# Power_Embedded_Board_Top.net
KiCad netlist of a schematic drawn in Altium Designer
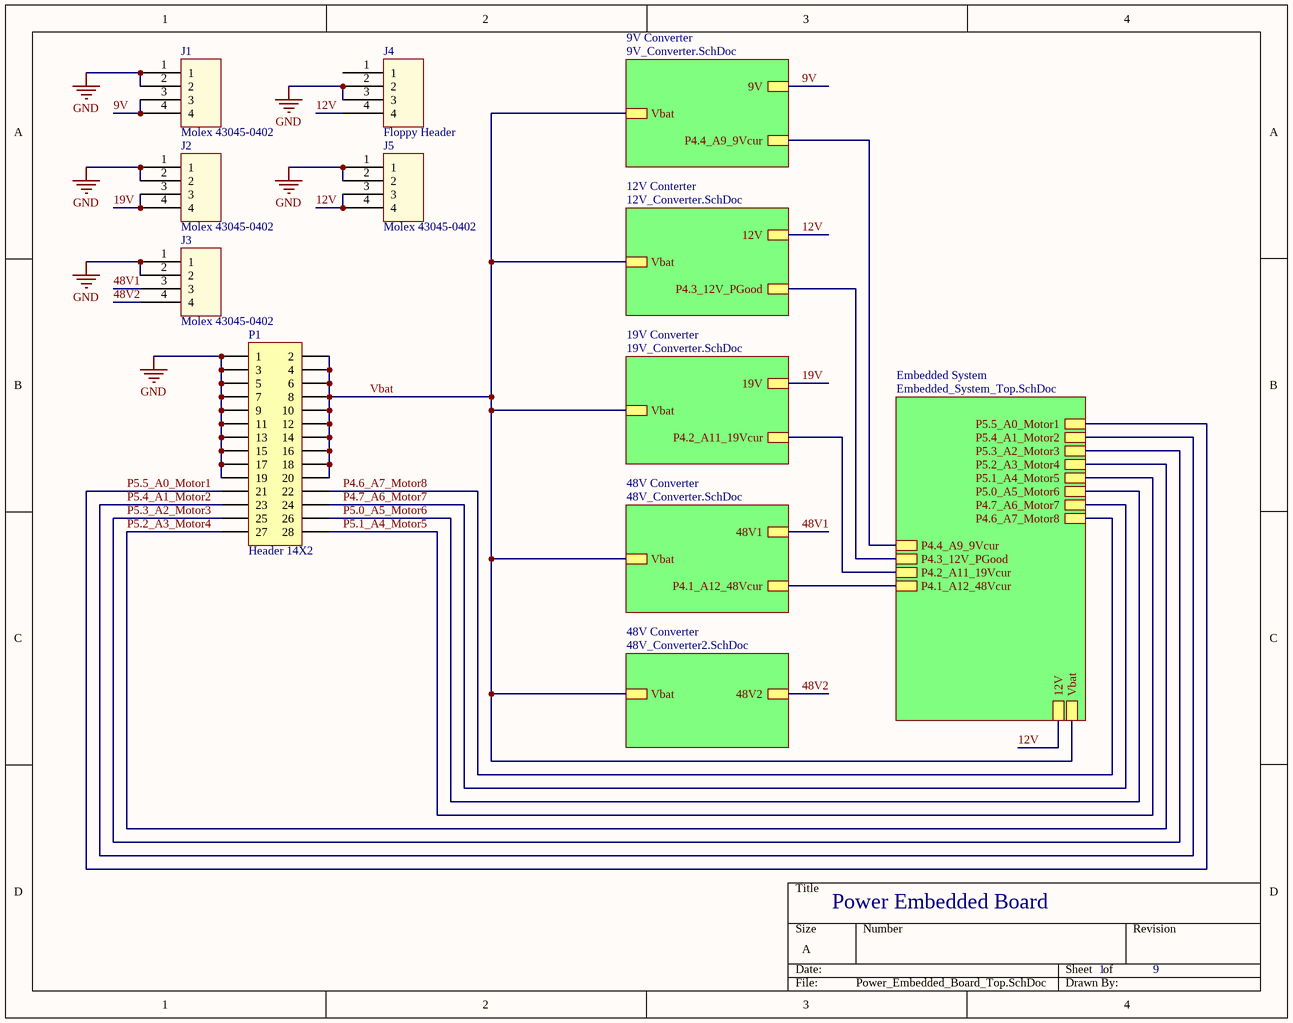
[diagram p0: Power_Embedded_Board_Top.SchDoc]

(export (version "E")
  (design (tool "Eeschema 10.0.6"))
  (components
    (comp (ref "J1")
      (value "Molex 43045-0402")
      (footprint "Molex43045-0402")
      (libsource (lib "Power_Embedded_Board_Library") (part "Molex43045-0402"))
    )
    (comp (ref "J2")
      (value "Molex 43045-0402")
      (footprint "Molex43045-0402")
      (libsource (lib "Power_Embedded_Board_Library") (part "Molex43045-0402"))
    )
    (comp (ref "J3")
      (value "Molex 43045-0402")
      (footprint "Molex43045-0402")
      (libsource (lib "Power_Embedded_Board_Library") (part "Molex43045-0402"))
    )
    (comp (ref "J4")
      (value "Floppy Header")
      (footprint "Header 1x4 12V")
      (libsource (lib "Power_Embedded_Board_Library") (part "Molex43045-0402"))
    )
    (comp (ref "J5")
      (value "Molex 43045-0402")
      (footprint "Molex43045-0402")
      (libsource (lib "Power_Embedded_Board_Library") (part "Molex43045-0402"))
    )
    (comp (ref "P1")
      (value "Header 14X2")
      (footprint "Header 2x14")
      (description "Header, 14-Pin, Dual row")
      (fields (field (name "PUBLISHER") "Altium Limited"))
      (libsource (lib "Miscellaneous Connectors") (part "Header 14X2"))
    )
  )
  (nets
    (net (code "1") (name "/9V") (class "Default")
      (node (ref "J1") (pin "3") (pinfunction "3_3") (pintype "passive"))
      (node (ref "J1") (pin "4") (pinfunction "4_4") (pintype "passive"))
    )
    (net (code "2") (name "/12V") (class "Default")
      (node (ref "J4") (pin "4") (pinfunction "4_4") (pintype "passive"))
      (node (ref "J5") (pin "3") (pinfunction "3_3") (pintype "passive"))
      (node (ref "J5") (pin "4") (pinfunction "4_4") (pintype "passive"))
    )
    (net (code "3") (name "/19V") (class "Default")
      (node (ref "J2") (pin "3") (pinfunction "3_3") (pintype "passive"))
      (node (ref "J2") (pin "4") (pinfunction "4_4") (pintype "passive"))
    )
    (net (code "4") (name "/48V1") (class "Default")
      (node (ref "J3") (pin "3") (pinfunction "3_3") (pintype "passive"))
    )
    (net (code "5") (name "/48V2") (class "Default")
      (node (ref "J3") (pin "4") (pinfunction "4_4") (pintype "passive"))
    )
    (net (code "10") (name "/P4.6_A7_Motor8") (class "Default")
      (node (ref "P1") (pin "22") (pinfunction "22_22") (pintype "passive"))
    )
    (net (code "11") (name "/P4.7_A6_Motor7") (class "Default")
      (node (ref "P1") (pin "24") (pinfunction "24_24") (pintype "passive"))
    )
    (net (code "12") (name "/P5.0_A5_Motor6") (class "Default")
      (node (ref "P1") (pin "26") (pinfunction "26_26") (pintype "passive"))
    )
    (net (code "13") (name "/P5.1_A4_Motor5") (class "Default")
      (node (ref "P1") (pin "28") (pinfunction "28_28") (pintype "passive"))
    )
    (net (code "14") (name "/P5.2_A3_Motor4") (class "Default")
      (node (ref "P1") (pin "27") (pinfunction "27_27") (pintype "passive"))
    )
    (net (code "15") (name "/P5.3_A2_Motor3") (class "Default")
      (node (ref "P1") (pin "25") (pinfunction "25_25") (pintype "passive"))
    )
    (net (code "16") (name "/P5.4_A1_Motor2") (class "Default")
      (node (ref "P1") (pin "23") (pinfunction "23_23") (pintype "passive"))
    )
    (net (code "17") (name "/P5.5_A0_Motor1") (class "Default")
      (node (ref "P1") (pin "21") (pinfunction "21_21") (pintype "passive"))
    )
    (net (code "18") (name "/Vbat") (class "Default")
      (node (ref "P1") (pin "10") (pinfunction "10_10") (pintype "passive"))
      (node (ref "P1") (pin "12") (pinfunction "12_12") (pintype "passive"))
      (node (ref "P1") (pin "14") (pinfunction "14_14") (pintype "passive"))
      (node (ref "P1") (pin "16") (pinfunction "16_16") (pintype "passive"))
      (node (ref "P1") (pin "18") (pinfunction "18_18") (pintype "passive"))
      (node (ref "P1") (pin "2") (pinfunction "2_2") (pintype "passive"))
      (node (ref "P1") (pin "20") (pinfunction "20_20") (pintype "passive"))
      (node (ref "P1") (pin "4") (pinfunction "4_4") (pintype "passive"))
      (node (ref "P1") (pin "6") (pinfunction "6_6") (pintype "passive"))
      (node (ref "P1") (pin "8") (pinfunction "8_8") (pintype "passive"))
    )
    (net (code "19") (name "GND") (class "Default")
      (node (ref "J1") (pin "1") (pinfunction "1_1") (pintype "passive"))
      (node (ref "J1") (pin "2") (pinfunction "2_2") (pintype "passive"))
      (node (ref "J2") (pin "1") (pinfunction "1_1") (pintype "passive"))
      (node (ref "J2") (pin "2") (pinfunction "2_2") (pintype "passive"))
      (node (ref "J3") (pin "1") (pinfunction "1_1") (pintype "passive"))
      (node (ref "J3") (pin "2") (pinfunction "2_2") (pintype "passive"))
      (node (ref "J4") (pin "2") (pinfunction "2_2") (pintype "passive"))
      (node (ref "J4") (pin "3") (pinfunction "3_3") (pintype "passive"))
      (node (ref "J5") (pin "1") (pinfunction "1_1") (pintype "passive"))
      (node (ref "J5") (pin "2") (pinfunction "2_2") (pintype "passive"))
      (node (ref "P1") (pin "1") (pinfunction "1_1") (pintype "passive"))
      (node (ref "P1") (pin "11") (pinfunction "11_11") (pintype "passive"))
      (node (ref "P1") (pin "13") (pinfunction "13_13") (pintype "passive"))
      (node (ref "P1") (pin "15") (pinfunction "15_15") (pintype "passive"))
      (node (ref "P1") (pin "17") (pinfunction "17_17") (pintype "passive"))
      (node (ref "P1") (pin "19") (pinfunction "19_19") (pintype "passive"))
      (node (ref "P1") (pin "3") (pinfunction "3_3") (pintype "passive"))
      (node (ref "P1") (pin "5") (pinfunction "5_5") (pintype "passive"))
      (node (ref "P1") (pin "7") (pinfunction "7_7") (pintype "passive"))
      (node (ref "P1") (pin "9") (pinfunction "9_9") (pintype "passive"))
    )
    (net (code "20") (name "unconnected-(J4-Pad1)") (class "Default")
      (node (ref "J4") (pin "1") (pinfunction "1_1") (pintype "passive"))
    )
  )
)
